# oeuil.net
KiCad netlist of a schematic drawn in EAGLE
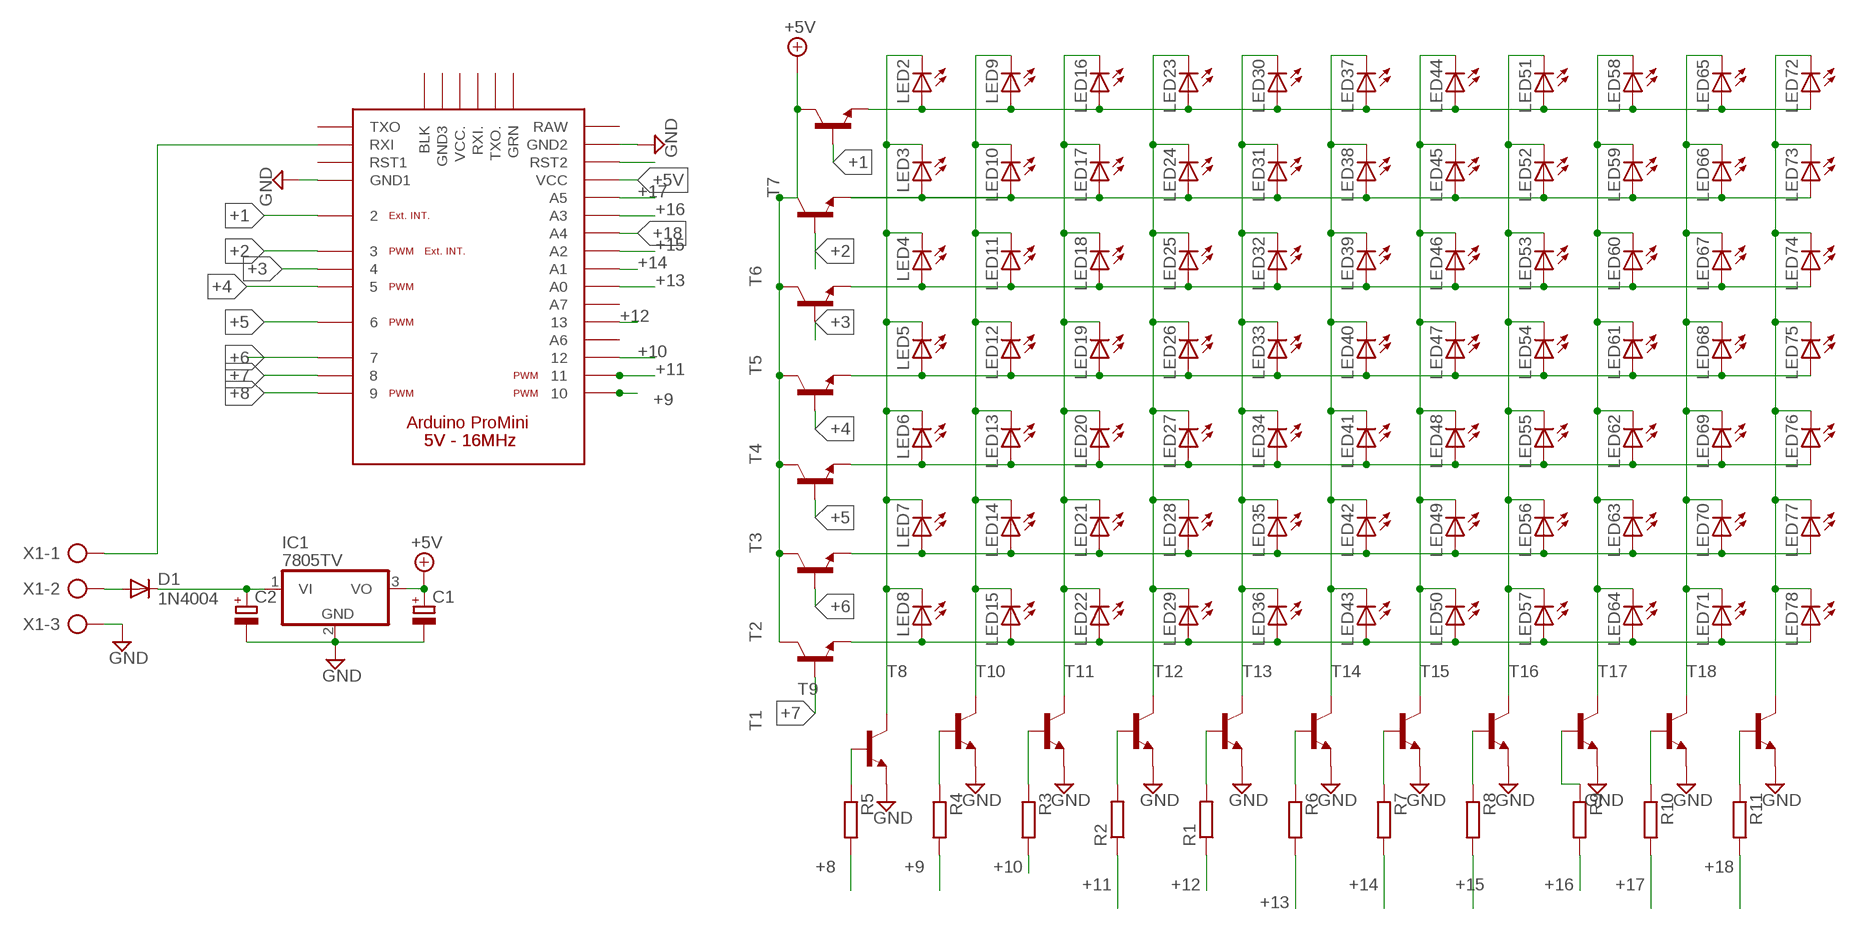
[diagram p0: schematic, sheet 1]

(export (version "E")
  (design (tool "Eeschema 10.0.6"))
  (components
    (comp (ref "C1")
      (value "CPOL-EUE2,5-6E")
      (footprint "eagle-import:E2,5-6E")
      (libsource (lib "eagle-import") (part "CPOL-EUE2,5-6E"))
    )
    (comp (ref "C2")
      (value "CPOL-EUE2,5-6E")
      (footprint "eagle-import:E2,5-6E")
      (libsource (lib "eagle-import") (part "CPOL-EUE2,5-6E"))
    )
    (comp (ref "D1")
      (value "1N4004")
      (footprint "eagle-import:DO41-10")
      (libsource (lib "eagle-import") (part "1N4004"))
    )
    (comp (ref "IC1")
      (value "7805TV")
      (footprint "eagle-import:TO220V")
      (libsource (lib "eagle-import") (part "78TV05"))
    )
    (comp (ref "LED2")
      (value "LED3MM")
      (footprint "eagle-import:LED3MM")
      (libsource (lib "eagle-import") (part "LED3MM"))
    )
    (comp (ref "LED3")
      (value "LED3MM")
      (footprint "eagle-import:LED3MM")
      (libsource (lib "eagle-import") (part "LED3MM"))
    )
    (comp (ref "LED4")
      (value "LED3MM")
      (footprint "eagle-import:LED3MM")
      (libsource (lib "eagle-import") (part "LED3MM"))
    )
    (comp (ref "LED5")
      (value "LED3MM")
      (footprint "eagle-import:LED3MM")
      (libsource (lib "eagle-import") (part "LED3MM"))
    )
    (comp (ref "LED6")
      (value "LED3MM")
      (footprint "eagle-import:LED3MM")
      (libsource (lib "eagle-import") (part "LED3MM"))
    )
    (comp (ref "LED7")
      (value "LED3MM")
      (footprint "eagle-import:LED3MM")
      (libsource (lib "eagle-import") (part "LED3MM"))
    )
    (comp (ref "LED8")
      (value "LED3MM")
      (footprint "eagle-import:LED3MM")
      (libsource (lib "eagle-import") (part "LED3MM"))
    )
    (comp (ref "LED9")
      (value "LED3MM")
      (footprint "eagle-import:LED3MM")
      (libsource (lib "eagle-import") (part "LED3MM"))
    )
    (comp (ref "LED10")
      (value "LED3MM")
      (footprint "eagle-import:LED3MM")
      (libsource (lib "eagle-import") (part "LED3MM"))
    )
    (comp (ref "LED11")
      (value "LED3MM")
      (footprint "eagle-import:LED3MM")
      (libsource (lib "eagle-import") (part "LED3MM"))
    )
    (comp (ref "LED12")
      (value "LED3MM")
      (footprint "eagle-import:LED3MM")
      (libsource (lib "eagle-import") (part "LED3MM"))
    )
    (comp (ref "LED13")
      (value "LED3MM")
      (footprint "eagle-import:LED3MM")
      (libsource (lib "eagle-import") (part "LED3MM"))
    )
    (comp (ref "LED14")
      (value "LED3MM")
      (footprint "eagle-import:LED3MM")
      (libsource (lib "eagle-import") (part "LED3MM"))
    )
    (comp (ref "LED15")
      (value "LED3MM")
      (footprint "eagle-import:LED3MM")
      (libsource (lib "eagle-import") (part "LED3MM"))
    )
    (comp (ref "LED16")
      (value "LED3MM")
      (footprint "eagle-import:LED3MM")
      (libsource (lib "eagle-import") (part "LED3MM"))
    )
    (comp (ref "LED17")
      (value "LED3MM")
      (footprint "eagle-import:LED3MM")
      (libsource (lib "eagle-import") (part "LED3MM"))
    )
    (comp (ref "LED18")
      (value "LED3MM")
      (footprint "eagle-import:LED3MM")
      (libsource (lib "eagle-import") (part "LED3MM"))
    )
    (comp (ref "LED19")
      (value "LED3MM")
      (footprint "eagle-import:LED3MM")
      (libsource (lib "eagle-import") (part "LED3MM"))
    )
    (comp (ref "LED20")
      (value "LED3MM")
      (footprint "eagle-import:LED3MM")
      (libsource (lib "eagle-import") (part "LED3MM"))
    )
    (comp (ref "LED21")
      (value "LED3MM")
      (footprint "eagle-import:LED3MM")
      (libsource (lib "eagle-import") (part "LED3MM"))
    )
    (comp (ref "LED22")
      (value "LED3MM")
      (footprint "eagle-import:LED3MM")
      (libsource (lib "eagle-import") (part "LED3MM"))
    )
    (comp (ref "LED23")
      (value "LED3MM")
      (footprint "eagle-import:LED3MM")
      (libsource (lib "eagle-import") (part "LED3MM"))
    )
    (comp (ref "LED24")
      (value "LED3MM")
      (footprint "eagle-import:LED3MM")
      (libsource (lib "eagle-import") (part "LED3MM"))
    )
    (comp (ref "LED25")
      (value "LED3MM")
      (footprint "eagle-import:LED3MM")
      (libsource (lib "eagle-import") (part "LED3MM"))
    )
    (comp (ref "LED26")
      (value "LED3MM")
      (footprint "eagle-import:LED3MM")
      (libsource (lib "eagle-import") (part "LED3MM"))
    )
    (comp (ref "LED27")
      (value "LED3MM")
      (footprint "eagle-import:LED3MM")
      (libsource (lib "eagle-import") (part "LED3MM"))
    )
    (comp (ref "LED28")
      (value "LED3MM")
      (footprint "eagle-import:LED3MM")
      (libsource (lib "eagle-import") (part "LED3MM"))
    )
    (comp (ref "LED29")
      (value "LED3MM")
      (footprint "eagle-import:LED3MM")
      (libsource (lib "eagle-import") (part "LED3MM"))
    )
    (comp (ref "LED30")
      (value "LED3MM")
      (footprint "eagle-import:LED3MM")
      (libsource (lib "eagle-import") (part "LED3MM"))
    )
    (comp (ref "LED31")
      (value "LED3MM")
      (footprint "eagle-import:LED3MM")
      (libsource (lib "eagle-import") (part "LED3MM"))
    )
    (comp (ref "LED32")
      (value "LED3MM")
      (footprint "eagle-import:LED3MM")
      (libsource (lib "eagle-import") (part "LED3MM"))
    )
    (comp (ref "LED33")
      (value "LED3MM")
      (footprint "eagle-import:LED3MM")
      (libsource (lib "eagle-import") (part "LED3MM"))
    )
    (comp (ref "LED34")
      (value "LED3MM")
      (footprint "eagle-import:LED3MM")
      (libsource (lib "eagle-import") (part "LED3MM"))
    )
    (comp (ref "LED35")
      (value "LED3MM")
      (footprint "eagle-import:LED3MM")
      (libsource (lib "eagle-import") (part "LED3MM"))
    )
    (comp (ref "LED36")
      (value "LED3MM")
      (footprint "eagle-import:LED3MM")
      (libsource (lib "eagle-import") (part "LED3MM"))
    )
    (comp (ref "LED37")
      (value "LED3MM")
      (footprint "eagle-import:LED3MM")
      (libsource (lib "eagle-import") (part "LED3MM"))
    )
    (comp (ref "LED38")
      (value "LED3MM")
      (footprint "eagle-import:LED3MM")
      (libsource (lib "eagle-import") (part "LED3MM"))
    )
    (comp (ref "LED39")
      (value "LED3MM")
      (footprint "eagle-import:LED3MM")
      (libsource (lib "eagle-import") (part "LED3MM"))
    )
    (comp (ref "LED40")
      (value "LED3MM")
      (footprint "eagle-import:LED3MM")
      (libsource (lib "eagle-import") (part "LED3MM"))
    )
    (comp (ref "LED41")
      (value "LED3MM")
      (footprint "eagle-import:LED3MM")
      (libsource (lib "eagle-import") (part "LED3MM"))
    )
    (comp (ref "LED42")
      (value "LED3MM")
      (footprint "eagle-import:LED3MM")
      (libsource (lib "eagle-import") (part "LED3MM"))
    )
    (comp (ref "LED43")
      (value "LED3MM")
      (footprint "eagle-import:LED3MM")
      (libsource (lib "eagle-import") (part "LED3MM"))
    )
    (comp (ref "LED44")
      (value "LED3MM")
      (footprint "eagle-import:LED3MM")
      (libsource (lib "eagle-import") (part "LED3MM"))
    )
    (comp (ref "LED45")
      (value "LED3MM")
      (footprint "eagle-import:LED3MM")
      (libsource (lib "eagle-import") (part "LED3MM"))
    )
    (comp (ref "LED46")
      (value "LED3MM")
      (footprint "eagle-import:LED3MM")
      (libsource (lib "eagle-import") (part "LED3MM"))
    )
    (comp (ref "LED47")
      (value "LED3MM")
      (footprint "eagle-import:LED3MM")
      (libsource (lib "eagle-import") (part "LED3MM"))
    )
    (comp (ref "LED48")
      (value "LED3MM")
      (footprint "eagle-import:LED3MM")
      (libsource (lib "eagle-import") (part "LED3MM"))
    )
    (comp (ref "LED49")
      (value "LED3MM")
      (footprint "eagle-import:LED3MM")
      (libsource (lib "eagle-import") (part "LED3MM"))
    )
    (comp (ref "LED50")
      (value "LED3MM")
      (footprint "eagle-import:LED3MM")
      (libsource (lib "eagle-import") (part "LED3MM"))
    )
    (comp (ref "LED51")
      (value "LED3MM")
      (footprint "eagle-import:LED3MM")
      (libsource (lib "eagle-import") (part "LED3MM"))
    )
    (comp (ref "LED52")
      (value "LED3MM")
      (footprint "eagle-import:LED3MM")
      (libsource (lib "eagle-import") (part "LED3MM"))
    )
    (comp (ref "LED53")
      (value "LED3MM")
      (footprint "eagle-import:LED3MM")
      (libsource (lib "eagle-import") (part "LED3MM"))
    )
    (comp (ref "LED54")
      (value "LED3MM")
      (footprint "eagle-import:LED3MM")
      (libsource (lib "eagle-import") (part "LED3MM"))
    )
    (comp (ref "LED55")
      (value "LED3MM")
      (footprint "eagle-import:LED3MM")
      (libsource (lib "eagle-import") (part "LED3MM"))
    )
    (comp (ref "LED56")
      (value "LED3MM")
      (footprint "eagle-import:LED3MM")
      (libsource (lib "eagle-import") (part "LED3MM"))
    )
    (comp (ref "LED57")
      (value "LED3MM")
      (footprint "eagle-import:LED3MM")
      (libsource (lib "eagle-import") (part "LED3MM"))
    )
    (comp (ref "LED58")
      (value "LED3MM")
      (footprint "eagle-import:LED3MM")
      (libsource (lib "eagle-import") (part "LED3MM"))
    )
    (comp (ref "LED59")
      (value "LED3MM")
      (footprint "eagle-import:LED3MM")
      (libsource (lib "eagle-import") (part "LED3MM"))
    )
    (comp (ref "LED60")
      (value "LED3MM")
      (footprint "eagle-import:LED3MM")
      (libsource (lib "eagle-import") (part "LED3MM"))
    )
    (comp (ref "LED61")
      (value "LED3MM")
      (footprint "eagle-import:LED3MM")
      (libsource (lib "eagle-import") (part "LED3MM"))
    )
    (comp (ref "LED62")
      (value "LED3MM")
      (footprint "eagle-import:LED3MM")
      (libsource (lib "eagle-import") (part "LED3MM"))
    )
    (comp (ref "LED63")
      (value "LED3MM")
      (footprint "eagle-import:LED3MM")
      (libsource (lib "eagle-import") (part "LED3MM"))
    )
    (comp (ref "LED64")
      (value "LED3MM")
      (footprint "eagle-import:LED3MM")
      (libsource (lib "eagle-import") (part "LED3MM"))
    )
    (comp (ref "LED65")
      (value "LED3MM")
      (footprint "eagle-import:LED3MM")
      (libsource (lib "eagle-import") (part "LED3MM"))
    )
    (comp (ref "LED66")
      (value "LED3MM")
      (footprint "eagle-import:LED3MM")
      (libsource (lib "eagle-import") (part "LED3MM"))
    )
    (comp (ref "LED67")
      (value "LED3MM")
      (footprint "eagle-import:LED3MM")
      (libsource (lib "eagle-import") (part "LED3MM"))
    )
    (comp (ref "LED68")
      (value "LED3MM")
      (footprint "eagle-import:LED3MM")
      (libsource (lib "eagle-import") (part "LED3MM"))
    )
    (comp (ref "LED69")
      (value "LED3MM")
      (footprint "eagle-import:LED3MM")
      (libsource (lib "eagle-import") (part "LED3MM"))
    )
    (comp (ref "LED70")
      (value "LED3MM")
      (footprint "eagle-import:LED3MM")
      (libsource (lib "eagle-import") (part "LED3MM"))
    )
    (comp (ref "LED71")
      (value "LED3MM")
      (footprint "eagle-import:LED3MM")
      (libsource (lib "eagle-import") (part "LED3MM"))
    )
    (comp (ref "LED72")
      (value "LED3MM")
      (footprint "eagle-import:LED3MM")
      (libsource (lib "eagle-import") (part "LED3MM"))
    )
    (comp (ref "LED73")
      (value "LED3MM")
      (footprint "eagle-import:LED3MM")
      (libsource (lib "eagle-import") (part "LED3MM"))
    )
    (comp (ref "LED74")
      (value "LED3MM")
      (footprint "eagle-import:LED3MM")
      (libsource (lib "eagle-import") (part "LED3MM"))
    )
    (comp (ref "LED75")
      (value "LED3MM")
      (footprint "eagle-import:LED3MM")
      (libsource (lib "eagle-import") (part "LED3MM"))
    )
    (comp (ref "LED76")
      (value "LED3MM")
      (footprint "eagle-import:LED3MM")
      (libsource (lib "eagle-import") (part "LED3MM"))
    )
    (comp (ref "LED77")
      (value "LED3MM")
      (footprint "eagle-import:LED3MM")
      (libsource (lib "eagle-import") (part "LED3MM"))
    )
    (comp (ref "LED78")
      (value "LED3MM")
      (footprint "eagle-import:LED3MM")
      (libsource (lib "eagle-import") (part "LED3MM"))
    )
    (comp (ref "R1")
      (value "R-EU_0207/2V")
      (footprint "eagle-import:0207_2V")
      (libsource (lib "eagle-import") (part "R-EU_0207/2V"))
    )
    (comp (ref "R2")
      (value "R-EU_0207/2V")
      (footprint "eagle-import:0207_2V")
      (libsource (lib "eagle-import") (part "R-EU_0207/2V"))
    )
    (comp (ref "R3")
      (value "R-EU_0207/2V")
      (footprint "eagle-import:0207_2V")
      (libsource (lib "eagle-import") (part "R-EU_0207/2V"))
    )
    (comp (ref "R4")
      (value "R-EU_0207/2V")
      (footprint "eagle-import:0207_2V")
      (libsource (lib "eagle-import") (part "R-EU_0207/2V"))
    )
    (comp (ref "R5")
      (value "R-EU_0207/2V")
      (footprint "eagle-import:0207_2V")
      (libsource (lib "eagle-import") (part "R-EU_0207/2V"))
    )
    (comp (ref "R6")
      (value "R-EU_0207/2V")
      (footprint "eagle-import:0207_2V")
      (libsource (lib "eagle-import") (part "R-EU_0207/2V"))
    )
    (comp (ref "R7")
      (value "R-EU_0207/2V")
      (footprint "eagle-import:0207_2V")
      (libsource (lib "eagle-import") (part "R-EU_0207/2V"))
    )
    (comp (ref "R8")
      (value "R-EU_0207/2V")
      (footprint "eagle-import:0207_2V")
      (libsource (lib "eagle-import") (part "R-EU_0207/2V"))
    )
    (comp (ref "R9")
      (value "R-EU_0207/2V")
      (footprint "eagle-import:0207_2V")
      (libsource (lib "eagle-import") (part "R-EU_0207/2V"))
    )
    (comp (ref "R10")
      (value "R-EU_0207/2V")
      (footprint "eagle-import:0207_2V")
      (libsource (lib "eagle-import") (part "R-EU_0207/2V"))
    )
    (comp (ref "R11")
      (value "R-EU_0207/2V")
      (footprint "eagle-import:0207_2V")
      (libsource (lib "eagle-import") (part "R-EU_0207/2V"))
    )
    (comp (ref "T1")
      (value "2N4124-NPN-TO92-CBE")
      (footprint "eagle-import:TO92-CBE")
      (libsource (lib "eagle-import") (part "-NPN-TO92-CBE2N4124"))
    )
    (comp (ref "T2")
      (value "2N4124-NPN-TO92-CBE")
      (footprint "eagle-import:TO92-CBE")
      (libsource (lib "eagle-import") (part "-NPN-TO92-CBE2N4124"))
    )
    (comp (ref "T3")
      (value "2N4124-NPN-TO92-CBE")
      (footprint "eagle-import:TO92-CBE")
      (libsource (lib "eagle-import") (part "-NPN-TO92-CBE2N4124"))
    )
    (comp (ref "T4")
      (value "2N4124-NPN-TO92-CBE")
      (footprint "eagle-import:TO92-CBE")
      (libsource (lib "eagle-import") (part "-NPN-TO92-CBE2N4124"))
    )
    (comp (ref "T5")
      (value "2N4124-NPN-TO92-CBE")
      (footprint "eagle-import:TO92-CBE")
      (libsource (lib "eagle-import") (part "-NPN-TO92-CBE2N4124"))
    )
    (comp (ref "T6")
      (value "2N4124-NPN-TO92-CBE")
      (footprint "eagle-import:TO92-CBE")
      (libsource (lib "eagle-import") (part "-NPN-TO92-CBE2N4124"))
    )
    (comp (ref "T7")
      (value "2N4124-NPN-TO92-CBE")
      (footprint "eagle-import:TO92-CBE")
      (libsource (lib "eagle-import") (part "-NPN-TO92-CBE2N4124"))
    )
    (comp (ref "T8")
      (value "2N4124-NPN-TO92-CBE")
      (footprint "eagle-import:TO92-CBE")
      (libsource (lib "eagle-import") (part "-NPN-TO92-CBE2N4124"))
    )
    (comp (ref "T9")
      (value "2N4124-NPN-TO92-CBE")
      (footprint "eagle-import:TO92-CBE")
      (libsource (lib "eagle-import") (part "-NPN-TO92-CBE2N4124"))
    )
    (comp (ref "T10")
      (value "2N4124-NPN-TO92-CBE")
      (footprint "eagle-import:TO92-CBE")
      (libsource (lib "eagle-import") (part "-NPN-TO92-CBE2N4124"))
    )
    (comp (ref "T11")
      (value "2N4124-NPN-TO92-CBE")
      (footprint "eagle-import:TO92-CBE")
      (libsource (lib "eagle-import") (part "-NPN-TO92-CBE2N4124"))
    )
    (comp (ref "T12")
      (value "2N4124-NPN-TO92-CBE")
      (footprint "eagle-import:TO92-CBE")
      (libsource (lib "eagle-import") (part "-NPN-TO92-CBE2N4124"))
    )
    (comp (ref "T13")
      (value "2N4124-NPN-TO92-CBE")
      (footprint "eagle-import:TO92-CBE")
      (libsource (lib "eagle-import") (part "-NPN-TO92-CBE2N4124"))
    )
    (comp (ref "T14")
      (value "2N4124-NPN-TO92-CBE")
      (footprint "eagle-import:TO92-CBE")
      (libsource (lib "eagle-import") (part "-NPN-TO92-CBE2N4124"))
    )
    (comp (ref "T15")
      (value "2N4124-NPN-TO92-CBE")
      (footprint "eagle-import:TO92-CBE")
      (libsource (lib "eagle-import") (part "-NPN-TO92-CBE2N4124"))
    )
    (comp (ref "T16")
      (value "2N4124-NPN-TO92-CBE")
      (footprint "eagle-import:TO92-CBE")
      (libsource (lib "eagle-import") (part "-NPN-TO92-CBE2N4124"))
    )
    (comp (ref "T17")
      (value "2N4124-NPN-TO92-CBE")
      (footprint "eagle-import:TO92-CBE")
      (libsource (lib "eagle-import") (part "-NPN-TO92-CBE2N4124"))
    )
    (comp (ref "T18")
      (value "2N4124-NPN-TO92-CBE")
      (footprint "eagle-import:TO92-CBE")
      (libsource (lib "eagle-import") (part "-NPN-TO92-CBE2N4124"))
    )
    (comp (ref "U$1")
      (value "ARDUINO_PRO_MINI")
      (footprint "eagle-import:ARDUINO_PRO_MINI")
      (libsource (lib "eagle-import") (part "ARDUINO_PRO_MINI"))
    )
    (comp (ref "X1")
      (value "AK300/3")
      (footprint "eagle-import:AK300_3")
      (libsource (lib "eagle-import") (part "AK300/3"))
    )
  )
  (nets
    (net (code "1") (name "+1") (class "Default")
      (node (ref "T7") (pin "B") (pinfunction "B_B") (pintype "passive"))
      (node (ref "U$1") (pin "2") (pinfunction "2_2") (pintype "bidirectional"))
    )
    (net (code "2") (name "+2") (class "Default")
      (node (ref "T6") (pin "B") (pinfunction "B_B") (pintype "passive"))
      (node (ref "U$1") (pin "3") (pinfunction "3_3") (pintype "bidirectional"))
    )
    (net (code "3") (name "+3") (class "Default")
      (node (ref "T5") (pin "B") (pinfunction "B_B") (pintype "passive"))
      (node (ref "U$1") (pin "4") (pinfunction "4_4") (pintype "bidirectional"))
    )
    (net (code "4") (name "+4") (class "Default")
      (node (ref "T4") (pin "B") (pinfunction "B_B") (pintype "passive"))
      (node (ref "U$1") (pin "5") (pinfunction "5_5") (pintype "bidirectional"))
    )
    (net (code "5") (name "+5") (class "Default")
      (node (ref "T3") (pin "B") (pinfunction "B_B") (pintype "passive"))
      (node (ref "U$1") (pin "6") (pinfunction "6_6") (pintype "bidirectional"))
    )
    (net (code "6") (name "+5V") (class "Default")
      (node (ref "C1") (pin "+") (pinfunction "+_+") (pintype "passive"))
      (node (ref "IC1") (pin "3") (pinfunction "VO_3") (pintype "passive"))
      (node (ref "T1") (pin "C") (pinfunction "C_C") (pintype "passive"))
      (node (ref "T2") (pin "C") (pinfunction "C_C") (pintype "passive"))
      (node (ref "T3") (pin "C") (pinfunction "C_C") (pintype "passive"))
      (node (ref "T4") (pin "C") (pinfunction "C_C") (pintype "passive"))
      (node (ref "T5") (pin "C") (pinfunction "C_C") (pintype "passive"))
      (node (ref "T6") (pin "C") (pinfunction "C_C") (pintype "passive"))
      (node (ref "T7") (pin "C") (pinfunction "C_C") (pintype "passive"))
      (node (ref "U$1") (pin "VCC1") (pinfunction "VCC_VCC1") (pintype "bidirectional"))
    )
    (net (code "7") (name "+6") (class "Default")
      (node (ref "T2") (pin "B") (pinfunction "B_B") (pintype "passive"))
      (node (ref "U$1") (pin "7") (pinfunction "7_7") (pintype "bidirectional"))
    )
    (net (code "8") (name "+7") (class "Default")
      (node (ref "T1") (pin "B") (pinfunction "B_B") (pintype "passive"))
      (node (ref "U$1") (pin "8") (pinfunction "8_8") (pintype "bidirectional"))
    )
    (net (code "9") (name "+8") (class "Default")
      (node (ref "R5") (pin "2") (pinfunction "2_2") (pintype "passive"))
      (node (ref "U$1") (pin "9") (pinfunction "9_9") (pintype "bidirectional"))
    )
    (net (code "10") (name "+18") (class "Default")
      (node (ref "R11") (pin "2") (pinfunction "2_2") (pintype "passive"))
      (node (ref "U$1") (pin "A4") (pinfunction "A4_A4") (pintype "bidirectional"))
    )
    (net (code "11") (name "/+9") (class "Default")
      (node (ref "R4") (pin "2") (pinfunction "2_2") (pintype "passive"))
      (node (ref "U$1") (pin "10") (pinfunction "10_10") (pintype "bidirectional"))
    )
    (net (code "12") (name "/+10") (class "Default")
      (node (ref "R3") (pin "2") (pinfunction "2_2") (pintype "passive"))
      (node (ref "U$1") (pin "12") (pinfunction "12_12") (pintype "bidirectional"))
    )
    (net (code "13") (name "/+11") (class "Default")
      (node (ref "R2") (pin "1") (pinfunction "1_1") (pintype "passive"))
      (node (ref "U$1") (pin "11") (pinfunction "11_11") (pintype "bidirectional"))
    )
    (net (code "14") (name "/+12") (class "Default")
      (node (ref "R1") (pin "1") (pinfunction "1_1") (pintype "passive"))
      (node (ref "U$1") (pin "13") (pinfunction "13_13") (pintype "bidirectional"))
    )
    (net (code "15") (name "/+13") (class "Default")
      (node (ref "R6") (pin "2") (pinfunction "2_2") (pintype "passive"))
      (node (ref "U$1") (pin "A0") (pinfunction "A0_A0") (pintype "bidirectional"))
    )
    (net (code "16") (name "/+14") (class "Default")
      (node (ref "R7") (pin "2") (pinfunction "2_2") (pintype "passive"))
      (node (ref "U$1") (pin "A1") (pinfunction "A1_A1") (pintype "bidirectional"))
    )
    (net (code "17") (name "/+15") (class "Default")
      (node (ref "R8") (pin "2") (pinfunction "2_2") (pintype "passive"))
      (node (ref "U$1") (pin "A2") (pinfunction "A2_A2") (pintype "bidirectional"))
    )
    (net (code "18") (name "/+16") (class "Default")
      (node (ref "R9") (pin "2") (pinfunction "2_2") (pintype "passive"))
      (node (ref "U$1") (pin "A3") (pinfunction "A3_A3") (pintype "bidirectional"))
    )
    (net (code "19") (name "/+17") (class "Default")
      (node (ref "R10") (pin "2") (pinfunction "2_2") (pintype "passive"))
      (node (ref "U$1") (pin "A5") (pinfunction "A5_A5") (pintype "bidirectional"))
    )
    (net (code "20") (name "GND") (class "Default")
      (node (ref "C1") (pin "-") (pinfunction "-_-") (pintype "passive"))
      (node (ref "C2") (pin "-") (pinfunction "-_-") (pintype "passive"))
      (node (ref "IC1") (pin "2") (pinfunction "GND_2") (pintype "passive"))
      (node (ref "T10") (pin "E") (pinfunction "E_E") (pintype "passive"))
      (node (ref "T11") (pin "E") (pinfunction "E_E") (pintype "passive"))
      (node (ref "T12") (pin "E") (pinfunction "E_E") (pintype "passive"))
      (node (ref "T13") (pin "E") (pinfunction "E_E") (pintype "passive"))
      (node (ref "T14") (pin "E") (pinfunction "E_E") (pintype "passive"))
      (node (ref "T15") (pin "E") (pinfunction "E_E") (pintype "passive"))
      (node (ref "T16") (pin "E") (pinfunction "E_E") (pintype "passive"))
      (node (ref "T17") (pin "E") (pinfunction "E_E") (pintype "passive"))
      (node (ref "T18") (pin "E") (pinfunction "E_E") (pintype "passive"))
      (node (ref "T8") (pin "E") (pinfunction "E_E") (pintype "passive"))
      (node (ref "T9") (pin "E") (pinfunction "E_E") (pintype "passive"))
      (node (ref "U$1") (pin "GND1") (pinfunction "GND1_GND1") (pintype "bidirectional"))
      (node (ref "U$1") (pin "GND2") (pinfunction "GND2_GND2") (pintype "bidirectional"))
      (node (ref "X1") (pin "3") (pinfunction "KL_3") (pintype "passive"))
    )
    (net (code "21") (name "Net-(IC1-VI)") (class "Default")
      (node (ref "C2") (pin "+") (pinfunction "+_+") (pintype "passive"))
      (node (ref "D1") (pin "C") (pinfunction "C_C") (pintype "passive"))
      (node (ref "IC1") (pin "1") (pinfunction "VI_1") (pintype "input"))
    )
    (net (code "22") (name "Net-(LED2-C)") (class "Default")
      (node (ref "LED2") (pin "K") (pinfunction "C_K") (pintype "passive"))
      (node (ref "LED3") (pin "K") (pinfunction "C_K") (pintype "passive"))
      (node (ref "LED4") (pin "K") (pinfunction "C_K") (pintype "passive"))
      (node (ref "LED5") (pin "K") (pinfunction "C_K") (pintype "passive"))
      (node (ref "LED6") (pin "K") (pinfunction "C_K") (pintype "passive"))
      (node (ref "LED7") (pin "K") (pinfunction "C_K") (pintype "passive"))
      (node (ref "LED8") (pin "K") (pinfunction "C_K") (pintype "passive"))
      (node (ref "T9") (pin "C") (pinfunction "C_C") (pintype "passive"))
    )
    (net (code "23") (name "Net-(LED10-C)") (class "Default")
      (node (ref "LED10") (pin "K") (pinfunction "C_K") (pintype "passive"))
      (node (ref "LED11") (pin "K") (pinfunction "C_K") (pintype "passive"))
      (node (ref "LED12") (pin "K") (pinfunction "C_K") (pintype "passive"))
      (node (ref "LED13") (pin "K") (pinfunction "C_K") (pintype "passive"))
      (node (ref "LED14") (pin "K") (pinfunction "C_K") (pintype "passive"))
      (node (ref "LED15") (pin "K") (pinfunction "C_K") (pintype "passive"))
      (node (ref "LED9") (pin "K") (pinfunction "C_K") (pintype "passive"))
      (node (ref "T8") (pin "C") (pinfunction "C_C") (pintype "passive"))
    )
    (net (code "24") (name "Net-(LED10-PadA)") (class "Default")
      (node (ref "LED10") (pin "A") (pinfunction "A_A") (pintype "passive"))
      (node (ref "LED17") (pin "A") (pinfunction "A_A") (pintype "passive"))
      (node (ref "LED24") (pin "A") (pinfunction "A_A") (pintype "passive"))
      (node (ref "LED3") (pin "A") (pinfunction "A_A") (pintype "passive"))
      (node (ref "LED31") (pin "A") (pinfunction "A_A") (pintype "passive"))
      (node (ref "LED38") (pin "A") (pinfunction "A_A") (pintype "passive"))
      (node (ref "LED45") (pin "A") (pinfunction "A_A") (pintype "passive"))
      (node (ref "LED52") (pin "A") (pinfunction "A_A") (pintype "passive"))
      (node (ref "LED59") (pin "A") (pinfunction "A_A") (pintype "passive"))
      (node (ref "LED66") (pin "A") (pinfunction "A_A") (pintype "passive"))
      (node (ref "LED73") (pin "A") (pinfunction "A_A") (pintype "passive"))
      (node (ref "T6") (pin "E") (pinfunction "E_E") (pintype "passive"))
    )
    (net (code "25") (name "Net-(LED11-PadA)") (class "Default")
      (node (ref "LED11") (pin "A") (pinfunction "A_A") (pintype "passive"))
      (node (ref "LED18") (pin "A") (pinfunction "A_A") (pintype "passive"))
      (node (ref "LED25") (pin "A") (pinfunction "A_A") (pintype "passive"))
      (node (ref "LED32") (pin "A") (pinfunction "A_A") (pintype "passive"))
      (node (ref "LED39") (pin "A") (pinfunction "A_A") (pintype "passive"))
      (node (ref "LED4") (pin "A") (pinfunction "A_A") (pintype "passive"))
      (node (ref "LED46") (pin "A") (pinfunction "A_A") (pintype "passive"))
      (node (ref "LED53") (pin "A") (pinfunction "A_A") (pintype "passive"))
      (node (ref "LED60") (pin "A") (pinfunction "A_A") (pintype "passive"))
      (node (ref "LED67") (pin "A") (pinfunction "A_A") (pintype "passive"))
      (node (ref "LED74") (pin "A") (pinfunction "A_A") (pintype "passive"))
      (node (ref "T5") (pin "E") (pinfunction "E_E") (pintype "passive"))
    )
    (net (code "26") (name "Net-(LED12-PadA)") (class "Default")
      (node (ref "LED12") (pin "A") (pinfunction "A_A") (pintype "passive"))
      (node (ref "LED19") (pin "A") (pinfunction "A_A") (pintype "passive"))
      (node (ref "LED26") (pin "A") (pinfunction "A_A") (pintype "passive"))
      (node (ref "LED33") (pin "A") (pinfunction "A_A") (pintype "passive"))
      (node (ref "LED40") (pin "A") (pinfunction "A_A") (pintype "passive"))
      (node (ref "LED47") (pin "A") (pinfunction "A_A") (pintype "passive"))
      (node (ref "LED5") (pin "A") (pinfunction "A_A") (pintype "passive"))
      (node (ref "LED54") (pin "A") (pinfunction "A_A") (pintype "passive"))
      (node (ref "LED61") (pin "A") (pinfunction "A_A") (pintype "passive"))
      (node (ref "LED68") (pin "A") (pinfunction "A_A") (pintype "passive"))
      (node (ref "LED75") (pin "A") (pinfunction "A_A") (pintype "passive"))
      (node (ref "T4") (pin "E") (pinfunction "E_E") (pintype "passive"))
    )
    (net (code "27") (name "Net-(LED13-PadA)") (class "Default")
      (node (ref "LED13") (pin "A") (pinfunction "A_A") (pintype "passive"))
      (node (ref "LED20") (pin "A") (pinfunction "A_A") (pintype "passive"))
      (node (ref "LED27") (pin "A") (pinfunction "A_A") (pintype "passive"))
      (node (ref "LED34") (pin "A") (pinfunction "A_A") (pintype "passive"))
      (node (ref "LED41") (pin "A") (pinfunction "A_A") (pintype "passive"))
      (node (ref "LED48") (pin "A") (pinfunction "A_A") (pintype "passive"))
      (node (ref "LED55") (pin "A") (pinfunction "A_A") (pintype "passive"))
      (node (ref "LED6") (pin "A") (pinfunction "A_A") (pintype "passive"))
      (node (ref "LED62") (pin "A") (pinfunction "A_A") (pintype "passive"))
      (node (ref "LED69") (pin "A") (pinfunction "A_A") (pintype "passive"))
      (node (ref "LED76") (pin "A") (pinfunction "A_A") (pintype "passive"))
      (node (ref "T3") (pin "E") (pinfunction "E_E") (pintype "passive"))
    )
    (net (code "28") (name "Net-(LED14-PadA)") (class "Default")
      (node (ref "LED14") (pin "A") (pinfunction "A_A") (pintype "passive"))
      (node (ref "LED21") (pin "A") (pinfunction "A_A") (pintype "passive"))
      (node (ref "LED28") (pin "A") (pinfunction "A_A") (pintype "passive"))
      (node (ref "LED35") (pin "A") (pinfunction "A_A") (pintype "passive"))
      (node (ref "LED42") (pin "A") (pinfunction "A_A") (pintype "passive"))
      (node (ref "LED49") (pin "A") (pinfunction "A_A") (pintype "passive"))
      (node (ref "LED56") (pin "A") (pinfunction "A_A") (pintype "passive"))
      (node (ref "LED63") (pin "A") (pinfunction "A_A") (pintype "passive"))
      (node (ref "LED7") (pin "A") (pinfunction "A_A") (pintype "passive"))
      (node (ref "LED70") (pin "A") (pinfunction "A_A") (pintype "passive"))
      (node (ref "LED77") (pin "A") (pinfunction "A_A") (pintype "passive"))
      (node (ref "T2") (pin "E") (pinfunction "E_E") (pintype "passive"))
    )
    (net (code "29") (name "Net-(LED15-PadA)") (class "Default")
      (node (ref "LED15") (pin "A") (pinfunction "A_A") (pintype "passive"))
      (node (ref "LED22") (pin "A") (pinfunction "A_A") (pintype "passive"))
      (node (ref "LED29") (pin "A") (pinfunction "A_A") (pintype "passive"))
      (node (ref "LED36") (pin "A") (pinfunction "A_A") (pintype "passive"))
      (node (ref "LED43") (pin "A") (pinfunction "A_A") (pintype "passive"))
      (node (ref "LED50") (pin "A") (pinfunction "A_A") (pintype "passive"))
      (node (ref "LED57") (pin "A") (pinfunction "A_A") (pintype "passive"))
      (node (ref "LED64") (pin "A") (pinfunction "A_A") (pintype "passive"))
      (node (ref "LED71") (pin "A") (pinfunction "A_A") (pintype "passive"))
      (node (ref "LED78") (pin "A") (pinfunction "A_A") (pintype "passive"))
      (node (ref "LED8") (pin "A") (pinfunction "A_A") (pintype "passive"))
      (node (ref "T1") (pin "E") (pinfunction "E_E") (pintype "passive"))
    )
    (net (code "30") (name "Net-(LED16-C)") (class "Default")
      (node (ref "LED16") (pin "K") (pinfunction "C_K") (pintype "passive"))
      (node (ref "LED17") (pin "K") (pinfunction "C_K") (pintype "passive"))
      (node (ref "LED18") (pin "K") (pinfunction "C_K") (pintype "passive"))
      (node (ref "LED19") (pin "K") (pinfunction "C_K") (pintype "passive"))
      (node (ref "LED20") (pin "K") (pinfunction "C_K") (pintype "passive"))
      (node (ref "LED21") (pin "K") (pinfunction "C_K") (pintype "passive"))
      (node (ref "LED22") (pin "K") (pinfunction "C_K") (pintype "passive"))
      (node (ref "T10") (pin "C") (pinfunction "C_C") (pintype "passive"))
    )
    (net (code "31") (name "Net-(LED16-PadA)") (class "Default")
      (node (ref "LED16") (pin "A") (pinfunction "A_A") (pintype "passive"))
      (node (ref "LED2") (pin "A") (pinfunction "A_A") (pintype "passive"))
      (node (ref "LED23") (pin "A") (pinfunction "A_A") (pintype "passive"))
      (node (ref "LED30") (pin "A") (pinfunction "A_A") (pintype "passive"))
      (node (ref "LED37") (pin "A") (pinfunction "A_A") (pintype "passive"))
      (node (ref "LED44") (pin "A") (pinfunction "A_A") (pintype "passive"))
      (node (ref "LED51") (pin "A") (pinfunction "A_A") (pintype "passive"))
      (node (ref "LED58") (pin "A") (pinfunction "A_A") (pintype "passive"))
      (node (ref "LED65") (pin "A") (pinfunction "A_A") (pintype "passive"))
      (node (ref "LED72") (pin "A") (pinfunction "A_A") (pintype "passive"))
      (node (ref "LED9") (pin "A") (pinfunction "A_A") (pintype "passive"))
      (node (ref "T7") (pin "E") (pinfunction "E_E") (pintype "passive"))
    )
    (net (code "32") (name "Net-(LED23-C)") (class "Default")
      (node (ref "LED23") (pin "K") (pinfunction "C_K") (pintype "passive"))
      (node (ref "LED24") (pin "K") (pinfunction "C_K") (pintype "passive"))
      (node (ref "LED25") (pin "K") (pinfunction "C_K") (pintype "passive"))
      (node (ref "LED26") (pin "K") (pinfunction "C_K") (pintype "passive"))
      (node (ref "LED27") (pin "K") (pinfunction "C_K") (pintype "passive"))
      (node (ref "LED28") (pin "K") (pinfunction "C_K") (pintype "passive"))
      (node (ref "LED29") (pin "K") (pinfunction "C_K") (pintype "passive"))
      (node (ref "T11") (pin "C") (pinfunction "C_C") (pintype "passive"))
    )
    (net (code "33") (name "Net-(LED30-C)") (class "Default")
      (node (ref "LED30") (pin "K") (pinfunction "C_K") (pintype "passive"))
      (node (ref "LED31") (pin "K") (pinfunction "C_K") (pintype "passive"))
      (node (ref "LED32") (pin "K") (pinfunction "C_K") (pintype "passive"))
      (node (ref "LED33") (pin "K") (pinfunction "C_K") (pintype "passive"))
      (node (ref "LED34") (pin "K") (pinfunction "C_K") (pintype "passive"))
      (node (ref "LED35") (pin "K") (pinfunction "C_K") (pintype "passive"))
      (node (ref "LED36") (pin "K") (pinfunction "C_K") (pintype "passive"))
      (node (ref "T12") (pin "C") (pinfunction "C_C") (pintype "passive"))
    )
    (net (code "34") (name "Net-(LED37-C)") (class "Default")
      (node (ref "LED37") (pin "K") (pinfunction "C_K") (pintype "passive"))
      (node (ref "LED38") (pin "K") (pinfunction "C_K") (pintype "passive"))
      (node (ref "LED39") (pin "K") (pinfunction "C_K") (pintype "passive"))
      (node (ref "LED40") (pin "K") (pinfunction "C_K") (pintype "passive"))
      (node (ref "LED41") (pin "K") (pinfunction "C_K") (pintype "passive"))
      (node (ref "LED42") (pin "K") (pinfunction "C_K") (pintype "passive"))
      (node (ref "LED43") (pin "K") (pinfunction "C_K") (pintype "passive"))
      (node (ref "T13") (pin "C") (pinfunction "C_C") (pintype "passive"))
    )
    (net (code "35") (name "Net-(LED44-C)") (class "Default")
      (node (ref "LED44") (pin "K") (pinfunction "C_K") (pintype "passive"))
      (node (ref "LED45") (pin "K") (pinfunction "C_K") (pintype "passive"))
      (node (ref "LED46") (pin "K") (pinfunction "C_K") (pintype "passive"))
      (node (ref "LED47") (pin "K") (pinfunction "C_K") (pintype "passive"))
      (node (ref "LED48") (pin "K") (pinfunction "C_K") (pintype "passive"))
      (node (ref "LED49") (pin "K") (pinfunction "C_K") (pintype "passive"))
      (node (ref "LED50") (pin "K") (pinfunction "C_K") (pintype "passive"))
      (node (ref "T14") (pin "C") (pinfunction "C_C") (pintype "passive"))
    )
    (net (code "36") (name "Net-(LED51-C)") (class "Default")
      (node (ref "LED51") (pin "K") (pinfunction "C_K") (pintype "passive"))
      (node (ref "LED52") (pin "K") (pinfunction "C_K") (pintype "passive"))
      (node (ref "LED53") (pin "K") (pinfunction "C_K") (pintype "passive"))
      (node (ref "LED54") (pin "K") (pinfunction "C_K") (pintype "passive"))
      (node (ref "LED55") (pin "K") (pinfunction "C_K") (pintype "passive"))
      (node (ref "LED56") (pin "K") (pinfunction "C_K") (pintype "passive"))
      (node (ref "LED57") (pin "K") (pinfunction "C_K") (pintype "passive"))
      (node (ref "T15") (pin "C") (pinfunction "C_C") (pintype "passive"))
    )
    (net (code "37") (name "Net-(LED58-C)") (class "Default")
      (node (ref "LED58") (pin "K") (pinfunction "C_K") (pintype "passive"))
      (node (ref "LED59") (pin "K") (pinfunction "C_K") (pintype "passive"))
      (node (ref "LED60") (pin "K") (pinfunction "C_K") (pintype "passive"))
      (node (ref "LED61") (pin "K") (pinfunction "C_K") (pintype "passive"))
      (node (ref "LED62") (pin "K") (pinfunction "C_K") (pintype "passive"))
      (node (ref "LED63") (pin "K") (pinfunction "C_K") (pintype "passive"))
      (node (ref "LED64") (pin "K") (pinfunction "C_K") (pintype "passive"))
      (node (ref "T16") (pin "C") (pinfunction "C_C") (pintype "passive"))
    )
    (net (code "38") (name "Net-(LED65-C)") (class "Default")
      (node (ref "LED65") (pin "K") (pinfunction "C_K") (pintype "passive"))
      (node (ref "LED66") (pin "K") (pinfunction "C_K") (pintype "passive"))
      (node (ref "LED67") (pin "K") (pinfunction "C_K") (pintype "passive"))
      (node (ref "LED68") (pin "K") (pinfunction "C_K") (pintype "passive"))
      (node (ref "LED69") (pin "K") (pinfunction "C_K") (pintype "passive"))
      (node (ref "LED70") (pin "K") (pinfunction "C_K") (pintype "passive"))
      (node (ref "LED71") (pin "K") (pinfunction "C_K") (pintype "passive"))
      (node (ref "T17") (pin "C") (pinfunction "C_C") (pintype "passive"))
    )
    (net (code "39") (name "Net-(LED72-C)") (class "Default")
      (node (ref "LED72") (pin "K") (pinfunction "C_K") (pintype "passive"))
      (node (ref "LED73") (pin "K") (pinfunction "C_K") (pintype "passive"))
      (node (ref "LED74") (pin "K") (pinfunction "C_K") (pintype "passive"))
      (node (ref "LED75") (pin "K") (pinfunction "C_K") (pintype "passive"))
      (node (ref "LED76") (pin "K") (pinfunction "C_K") (pintype "passive"))
      (node (ref "LED77") (pin "K") (pinfunction "C_K") (pintype "passive"))
      (node (ref "LED78") (pin "K") (pinfunction "C_K") (pintype "passive"))
      (node (ref "T18") (pin "C") (pinfunction "C_C") (pintype "passive"))
    )
    (net (code "40") (name "Net-(R1-Pad2)") (class "Default")
      (node (ref "R1") (pin "2") (pinfunction "2_2") (pintype "passive"))
      (node (ref "T12") (pin "B") (pinfunction "B_B") (pintype "passive"))
    )
    (net (code "41") (name "Net-(R2-Pad2)") (class "Default")
      (node (ref "R2") (pin "2") (pinfunction "2_2") (pintype "passive"))
      (node (ref "T11") (pin "B") (pinfunction "B_B") (pintype "passive"))
    )
    (net (code "42") (name "Net-(R3-Pad1)") (class "Default")
      (node (ref "R3") (pin "1") (pinfunction "1_1") (pintype "passive"))
      (node (ref "T10") (pin "B") (pinfunction "B_B") (pintype "passive"))
    )
    (net (code "43") (name "Net-(R4-Pad1)") (class "Default")
      (node (ref "R4") (pin "1") (pinfunction "1_1") (pintype "passive"))
      (node (ref "T8") (pin "B") (pinfunction "B_B") (pintype "passive"))
    )
    (net (code "44") (name "Net-(R5-Pad1)") (class "Default")
      (node (ref "R5") (pin "1") (pinfunction "1_1") (pintype "passive"))
      (node (ref "T9") (pin "B") (pinfunction "B_B") (pintype "passive"))
    )
    (net (code "45") (name "Net-(R6-Pad1)") (class "Default")
      (node (ref "R6") (pin "1") (pinfunction "1_1") (pintype "passive"))
      (node (ref "T13") (pin "B") (pinfunction "B_B") (pintype "passive"))
    )
    (net (code "46") (name "Net-(R7-Pad1)") (class "Default")
      (node (ref "R7") (pin "1") (pinfunction "1_1") (pintype "passive"))
      (node (ref "T14") (pin "B") (pinfunction "B_B") (pintype "passive"))
    )
    (net (code "47") (name "Net-(R8-Pad1)") (class "Default")
      (node (ref "R8") (pin "1") (pinfunction "1_1") (pintype "passive"))
      (node (ref "T15") (pin "B") (pinfunction "B_B") (pintype "passive"))
    )
    (net (code "48") (name "Net-(R9-Pad1)") (class "Default")
      (node (ref "R9") (pin "1") (pinfunction "1_1") (pintype "passive"))
      (node (ref "T16") (pin "B") (pinfunction "B_B") (pintype "passive"))
    )
    (net (code "49") (name "Net-(R10-Pad1)") (class "Default")
      (node (ref "R10") (pin "1") (pinfunction "1_1") (pintype "passive"))
      (node (ref "T17") (pin "B") (pinfunction "B_B") (pintype "passive"))
    )
    (net (code "50") (name "Net-(R11-Pad1)") (class "Default")
      (node (ref "R11") (pin "1") (pinfunction "1_1") (pintype "passive"))
      (node (ref "T18") (pin "B") (pinfunction "B_B") (pintype "passive"))
    )
    (net (code "51") (name "Net-(U$1-RXI)") (class "Default")
      (node (ref "U$1") (pin "RXI1") (pinfunction "RXI_RXI1") (pintype "bidirectional"))
      (node (ref "X1") (pin "1") (pinfunction "KL_1") (pintype "passive"))
    )
    (net (code "52") (name "Net-(X1B-KL)") (class "Default")
      (node (ref "D1") (pin "A") (pinfunction "A_A") (pintype "passive"))
      (node (ref "X1") (pin "2") (pinfunction "KL_2") (pintype "passive"))
    )
    (net (code "53") (name "unconnected-(U$1-PadA6)") (class "Default")
      (node (ref "U$1") (pin "A6") (pinfunction "A6_A6") (pintype "bidirectional"))
    )
    (net (code "54") (name "unconnected-(U$1-PadA7)") (class "Default")
      (node (ref "U$1") (pin "A7") (pinfunction "A7_A7") (pintype "bidirectional"))
    )
    (net (code "55") (name "unconnected-(U$1-PadBLK)") (class "Default")
      (node (ref "U$1") (pin "BLK") (pinfunction "BLK_BLK") (pintype "bidirectional"))
    )
    (net (code "56") (name "unconnected-(U$1-PadGND3)") (class "Default")
      (node (ref "U$1") (pin "GND3") (pinfunction "GND3_GND3") (pintype "bidirectional"))
    )
    (net (code "57") (name "unconnected-(U$1-PadGRN)") (class "Default")
      (node (ref "U$1") (pin "GRN") (pinfunction "GRN_GRN") (pintype "bidirectional"))
    )
    (net (code "58") (name "unconnected-(U$1-PadRAW)") (class "Default")
      (node (ref "U$1") (pin "RAW") (pinfunction "RAW_RAW") (pintype "bidirectional"))
    )
    (net (code "59") (name "unconnected-(U$1-PadRST1)") (class "Default")
      (node (ref "U$1") (pin "RST1") (pinfunction "RST1_RST1") (pintype "bidirectional"))
    )
    (net (code "60") (name "unconnected-(U$1-PadRST2)") (class "Default")
      (node (ref "U$1") (pin "RST2") (pinfunction "RST2_RST2") (pintype "bidirectional"))
    )
    (net (code "61") (name "unconnected-(U$1-RXI.-PadRXI2)") (class "Default")
      (node (ref "U$1") (pin "RXI2") (pinfunction "RXI._RXI2") (pintype "bidirectional"))
    )
    (net (code "62") (name "unconnected-(U$1-TXO-PadTXO1)") (class "Default")
      (node (ref "U$1") (pin "TXO1") (pinfunction "TXO_TXO1") (pintype "bidirectional"))
    )
    (net (code "63") (name "unconnected-(U$1-TXO.-PadTXO2)") (class "Default")
      (node (ref "U$1") (pin "TXO2") (pinfunction "TXO._TXO2") (pintype "bidirectional"))
    )
    (net (code "64") (name "unconnected-(U$1-VCC.-PadVCC2)") (class "Default")
      (node (ref "U$1") (pin "VCC2") (pinfunction "VCC._VCC2") (pintype "bidirectional"))
    )
  )
)
